# Main_Megamind.net
KiCad netlist of a schematic drawn in Altium Designer
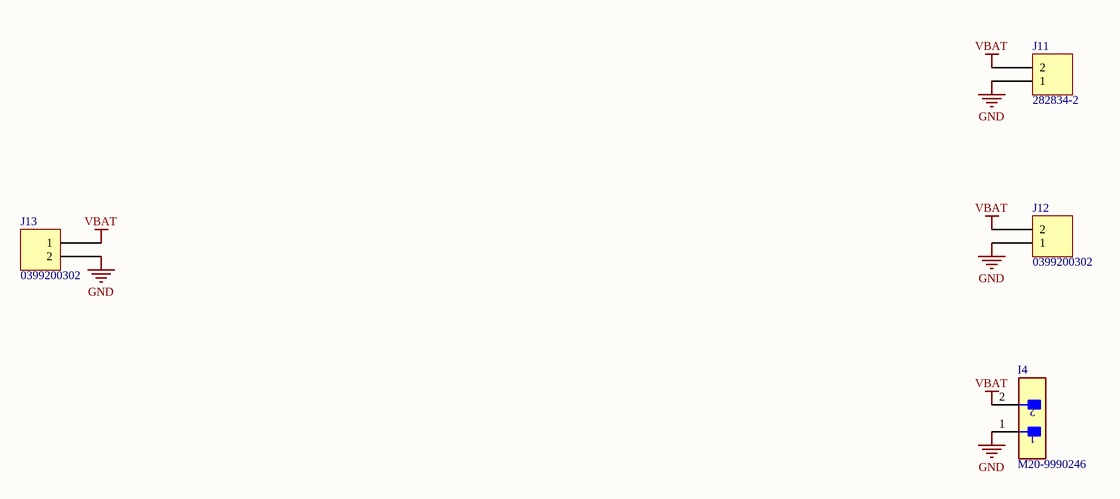
[diagram p0: Main_Megamind.SchDoc]

(export (version "E")
  (design (tool "Eeschema 10.0.6"))
  (components
    (comp (ref "I4")
      (value "M20-9990246")
      (footprint "FP-M20-9990246-MFG")
      (description "CONN HEADER VERT 2POS 2.54MM")
      (fields
        (field (name "OCTOPART") "https://octopart.com/m20-9990246-harwin-2590635")
        (field (name "MANUFACTURER") "Harwin")
      )
      (libsource (lib "Altium Content Vault") (part "3bc925449376181038e59eaffc5286c"))
    )
    (comp (ref "J11")
      (value "282834-2")
      (footprint "TE 282834-2")
      (description "TERM BLK 2P SIDE ENT 2.54MM PCB")
      (fields (field (name "MANUFACTURER") "TE Connectivity AMP Connectors") (field (name "VOLTAGE") "150V"))
      (libsource (lib "") (part "2 Pin_1"))
    )
    (comp (ref "J12")
      (value "0399200302")
      (footprint "MOLEX 0399200302")
      (description "TERM BLK 2P SIDE ENTRY 15MM PCB")
      (fields (field (name "MANUFACTURER") "Molex") (field (name "VOLTAGE") "600 V"))
      (libsource (lib "") (part "2 Pin_1"))
    )
    (comp (ref "J13")
      (value "0399200302")
      (footprint "MOLEX 0399200302")
      (description "TERM BLK 2P SIDE ENTRY 15MM PCB")
      (fields (field (name "MANUFACTURER") "Molex") (field (name "VOLTAGE") "600 V"))
      (libsource (lib "Celestial Altium Library - altium_library (2)") (part "2 Pin"))
    )
  )
  (nets
    (net (code "1") (name "GND") (class "Default")
      (node (ref "I4") (pin "1") (pinfunction "1_1") (pintype "passive"))
      (node (ref "J11") (pin "1") (pinfunction "1_1") (pintype "passive"))
      (node (ref "J12") (pin "1") (pinfunction "1_1") (pintype "passive"))
      (node (ref "J13") (pin "2") (pinfunction "2_2") (pintype "passive"))
    )
    (net (code "2") (name "VBAT") (class "Default")
      (node (ref "I4") (pin "2") (pinfunction "2_2") (pintype "passive"))
      (node (ref "J11") (pin "2") (pinfunction "2_2") (pintype "passive"))
      (node (ref "J12") (pin "2") (pinfunction "2_2") (pintype "passive"))
      (node (ref "J13") (pin "1") (pinfunction "1_1") (pintype "passive"))
    )
  )
)
